# RA64500_jc20_rotary2.net
KiCad netlist of a schematic drawn in Altium Designer
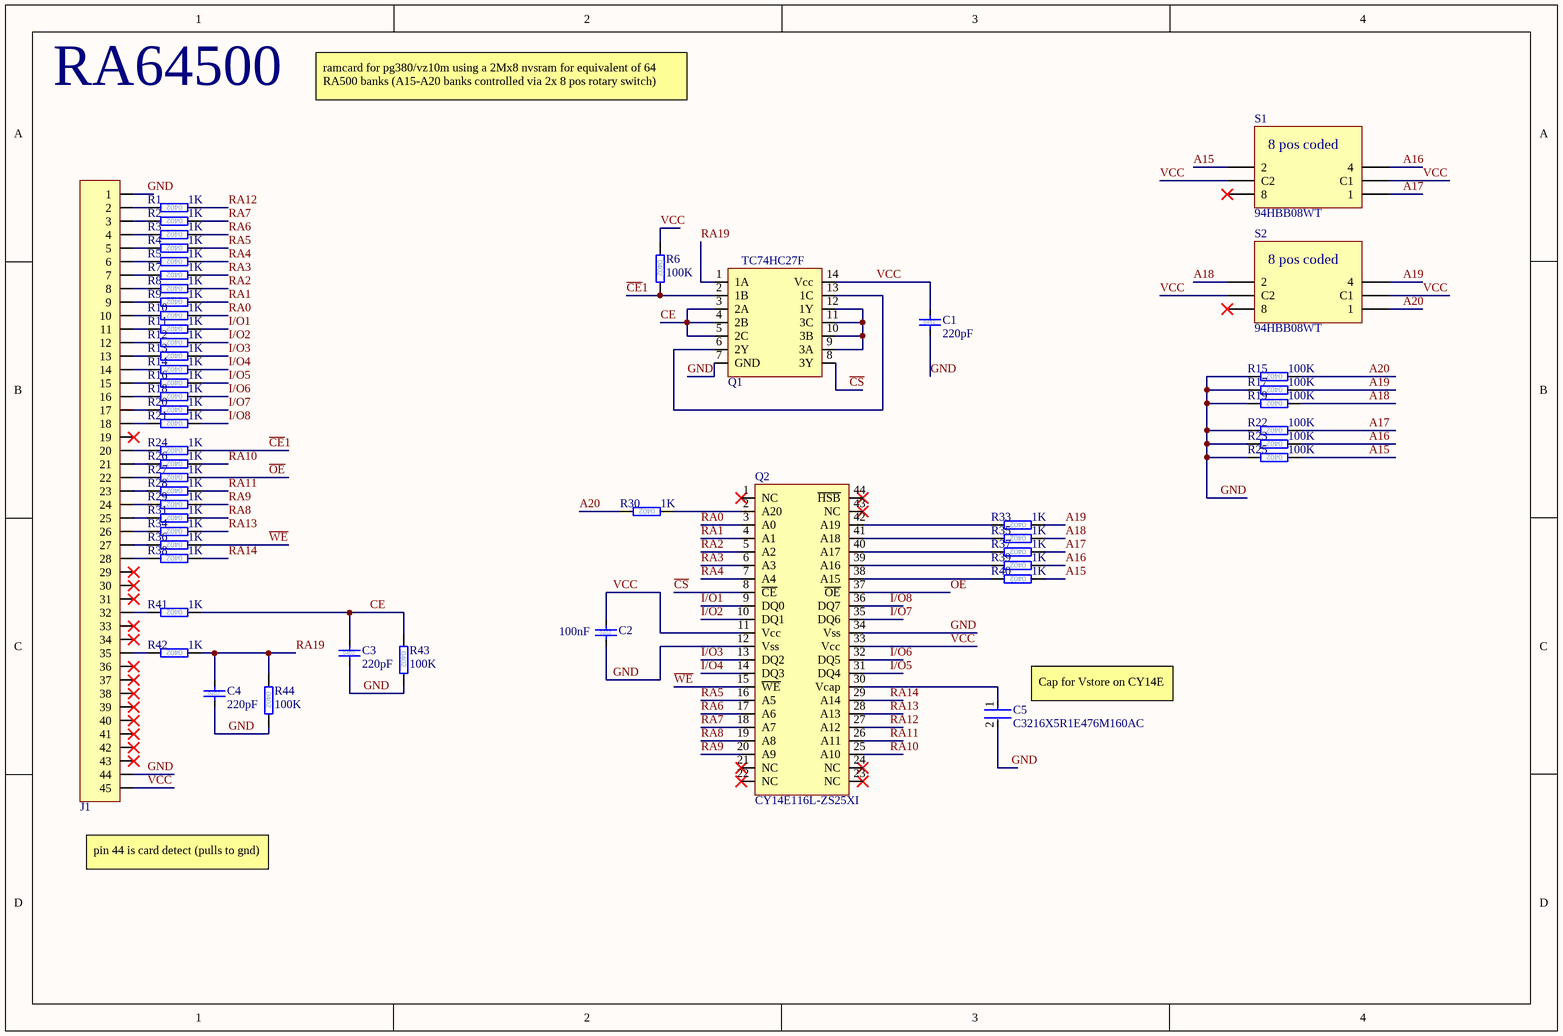
[diagram p0: RA64500_jc20_rotary2.SchDoc]

(export (version "E")
  (design (tool "Eeschema 10.0.6"))
  (components
    (comp (ref "C1")
      (value "220pF")
      (footprint "0402")
      (description "0402 220pF")
      (libsource (lib "ra500") (part "0402 Cap"))
    )
    (comp (ref "C2")
      (value "100nF")
      (footprint "0402")
      (description "0402 100nF")
      (libsource (lib "ra500") (part "0402 Cap"))
    )
    (comp (ref "C3")
      (value "220pF")
      (footprint "0402")
      (description "0402 220pF")
      (libsource (lib "ra500") (part "0402 Cap"))
    )
    (comp (ref "C4")
      (value "220pF")
      (footprint "0402")
      (description "0402 220pF")
      (libsource (lib "ra500") (part "0402 Cap"))
    )
    (comp (ref "C5")
      (value "C3216X5R1E476M160AC")
      (footprint "FP-C3216-160-0_2-MFG")
      (description "Multilayer Ceramic Capacitors 47uF ±20% 25V X5R SMD 1206")
      (fields (field (name "VOLTAGE") "25V") (field (name "TOLERANCE") "20%"))
      (libsource (lib "Altium Content Vault") (part "11868f565c42a9108669ba33697ecf6"))
    )
    (comp (ref "J1")
      (value "JC20-C45S-F1-A1")
      (footprint "JC20-C45S-F1-A1")
      (description "45 Pin 1mm pitch connector")
      (libsource (lib "ra500") (part "JC20-C45S-F1-A1"))
    )
    (comp (ref "Q1")
      (value "TC74HC27F")
      (footprint "SOP127P780X190-14N")
      (description "Triple 3-input NOR Gate")
      (libsource (lib "ra500") (part "TC74HC27F"))
    )
    (comp (ref "Q2")
      (value "CY14E116L-ZS25XI")
      (footprint "SOP80P1183X119-44N")
      (description "2Mx8 Bit nvSRAM")
      (libsource (lib "ra500") (part "CY14E116L-ZS25XI"))
    )
    (comp (ref "R1")
      (value "1K")
      (footprint "0402")
      (description "0402 1K")
      (libsource (lib "ra500") (part "0402 Res"))
    )
    (comp (ref "R2")
      (value "1K")
      (footprint "0402")
      (description "0402 1K")
      (libsource (lib "ra500") (part "0402 Res"))
    )
    (comp (ref "R3")
      (value "1K")
      (footprint "0402")
      (description "0402 1K")
      (libsource (lib "ra500") (part "0402 Res"))
    )
    (comp (ref "R4")
      (value "1K")
      (footprint "0402")
      (description "0402 1K")
      (libsource (lib "ra500") (part "0402 Res"))
    )
    (comp (ref "R5")
      (value "1K")
      (footprint "0402")
      (description "0402 1K")
      (libsource (lib "ra500") (part "0402 Res"))
    )
    (comp (ref "R6")
      (value "100K")
      (footprint "0402")
      (description "0402 100K")
      (libsource (lib "ra500") (part "0402 Res"))
    )
    (comp (ref "R7")
      (value "1K")
      (footprint "0402")
      (description "0402 1K")
      (libsource (lib "ra500") (part "0402 Res"))
    )
    (comp (ref "R8")
      (value "1K")
      (footprint "0402")
      (description "0402 1K")
      (libsource (lib "ra500") (part "0402 Res"))
    )
    (comp (ref "R9")
      (value "1K")
      (footprint "0402")
      (description "0402 1K")
      (libsource (lib "ra500") (part "0402 Res"))
    )
    (comp (ref "R10")
      (value "1K")
      (footprint "0402")
      (description "0402 1K")
      (libsource (lib "ra500") (part "0402 Res"))
    )
    (comp (ref "R11")
      (value "1K")
      (footprint "0402")
      (description "0402 1K")
      (libsource (lib "ra500") (part "0402 Res"))
    )
    (comp (ref "R12")
      (value "1K")
      (footprint "0402")
      (description "0402 1K")
      (libsource (lib "ra500") (part "0402 Res"))
    )
    (comp (ref "R13")
      (value "1K")
      (footprint "0402")
      (description "0402 1K")
      (libsource (lib "ra500") (part "0402 Res"))
    )
    (comp (ref "R14")
      (value "1K")
      (footprint "0402")
      (description "0402 1K")
      (libsource (lib "ra500") (part "0402 Res"))
    )
    (comp (ref "R15")
      (value "100K")
      (footprint "0402")
      (description "0402 100K")
      (libsource (lib "ra500") (part "0402 Res"))
    )
    (comp (ref "R16")
      (value "1K")
      (footprint "0402")
      (description "0402 1K")
      (libsource (lib "ra500") (part "0402 Res"))
    )
    (comp (ref "R17")
      (value "100K")
      (footprint "0402")
      (description "0402 100K")
      (libsource (lib "ra500") (part "0402 Res"))
    )
    (comp (ref "R18")
      (value "1K")
      (footprint "0402")
      (description "0402 1K")
      (libsource (lib "ra500") (part "0402 Res"))
    )
    (comp (ref "R19")
      (value "100K")
      (footprint "0402")
      (description "0402 100K")
      (libsource (lib "ra500") (part "0402 Res"))
    )
    (comp (ref "R20")
      (value "1K")
      (footprint "0402")
      (description "0402 1K")
      (libsource (lib "ra500") (part "0402 Res"))
    )
    (comp (ref "R21")
      (value "1K")
      (footprint "0402")
      (description "0402 1K")
      (libsource (lib "ra500") (part "0402 Res"))
    )
    (comp (ref "R22")
      (value "100K")
      (footprint "0402")
      (description "0402 100K")
      (libsource (lib "ra500") (part "0402 Res"))
    )
    (comp (ref "R23")
      (value "100K")
      (footprint "0402")
      (description "0402 100K")
      (libsource (lib "ra500") (part "0402 Res"))
    )
    (comp (ref "R24")
      (value "1K")
      (footprint "0402")
      (description "0402 1K")
      (libsource (lib "ra500") (part "0402 Res"))
    )
    (comp (ref "R25")
      (value "100K")
      (footprint "0402")
      (description "0402 100K")
      (libsource (lib "ra500") (part "0402 Res"))
    )
    (comp (ref "R26")
      (value "1K")
      (footprint "0402")
      (description "0402 1K")
      (libsource (lib "ra500") (part "0402 Res"))
    )
    (comp (ref "R27")
      (value "1K")
      (footprint "0402")
      (description "0402 1K")
      (libsource (lib "ra500") (part "0402 Res"))
    )
    (comp (ref "R28")
      (value "1K")
      (footprint "0402")
      (description "0402 1K")
      (libsource (lib "ra500") (part "0402 Res"))
    )
    (comp (ref "R29")
      (value "1K")
      (footprint "0402")
      (description "0402 1K")
      (libsource (lib "ra500") (part "0402 Res"))
    )
    (comp (ref "R30")
      (value "1K")
      (footprint "0402")
      (description "0402 1K")
      (libsource (lib "ra500") (part "0402 Res"))
    )
    (comp (ref "R31")
      (value "1K")
      (footprint "0402")
      (description "0402 1K")
      (libsource (lib "ra500") (part "0402 Res"))
    )
    (comp (ref "R33")
      (value "1K")
      (footprint "0402")
      (description "0402 1K")
      (libsource (lib "ra500") (part "0402 Res"))
    )
    (comp (ref "R34")
      (value "1K")
      (footprint "0402")
      (description "0402 1K")
      (libsource (lib "ra500") (part "0402 Res"))
    )
    (comp (ref "R35")
      (value "1K")
      (footprint "0402")
      (description "0402 1K")
      (libsource (lib "ra500") (part "0402 Res"))
    )
    (comp (ref "R36")
      (value "1K")
      (footprint "0402")
      (description "0402 1K")
      (libsource (lib "ra500") (part "0402 Res"))
    )
    (comp (ref "R37")
      (value "1K")
      (footprint "0402")
      (description "0402 1K")
      (libsource (lib "ra500") (part "0402 Res"))
    )
    (comp (ref "R38")
      (value "1K")
      (footprint "0402")
      (description "0402 1K")
      (libsource (lib "ra500") (part "0402 Res"))
    )
    (comp (ref "R39")
      (value "1K")
      (footprint "0402")
      (description "0402 1K")
      (libsource (lib "ra500") (part "0402 Res"))
    )
    (comp (ref "R40")
      (value "1K")
      (footprint "0402")
      (description "0402 1K")
      (libsource (lib "ra500") (part "0402 Res"))
    )
    (comp (ref "R41")
      (value "1K")
      (footprint "0402")
      (description "0402 1K")
      (libsource (lib "ra500") (part "0402 Res"))
    )
    (comp (ref "R42")
      (value "1K")
      (footprint "0402")
      (description "0402 1K")
      (libsource (lib "ra500") (part "0402 Res"))
    )
    (comp (ref "R43")
      (value "100K")
      (footprint "0402")
      (description "0402 100K")
      (libsource (lib "ra500") (part "0402 Res"))
    )
    (comp (ref "R44")
      (value "100K")
      (footprint "0402")
      (description "0402 100K")
      (libsource (lib "ra500") (part "0402 Res"))
    )
    (comp (ref "S1")
      (value "94HBB08WT")
      (footprint "94HBB08WT")
      (description "8 pos rotary coded switch")
      (libsource (lib "ra500") (part "94HBB08WT"))
    )
    (comp (ref "S2")
      (value "94HBB08WT")
      (footprint "94HBB08WT")
      (description "8 pos rotary coded switch")
      (libsource (lib "ra500") (part "94HBB08WT"))
    )
  )
  (nets
    (net (code "1") (name "/A15") (class "Default")
      (node (ref "R25") (pin "1") (pinfunction "R_1") (pintype "passive"))
      (node (ref "R40") (pin "1") (pinfunction "R_1") (pintype "passive"))
      (node (ref "S1") (pin "4") (pinfunction "2_4") (pintype "passive"))
    )
    (net (code "2") (name "/A16") (class "Default")
      (node (ref "R23") (pin "1") (pinfunction "R_1") (pintype "passive"))
      (node (ref "R39") (pin "1") (pinfunction "R_1") (pintype "passive"))
      (node (ref "S1") (pin "3") (pinfunction "4_3") (pintype "passive"))
    )
    (net (code "3") (name "/A17") (class "Default")
      (node (ref "R22") (pin "1") (pinfunction "R_1") (pintype "passive"))
      (node (ref "R37") (pin "1") (pinfunction "R_1") (pintype "passive"))
      (node (ref "S1") (pin "1") (pinfunction "1_1") (pintype "passive"))
    )
    (net (code "4") (name "/A18") (class "Default")
      (node (ref "R19") (pin "1") (pinfunction "R_1") (pintype "passive"))
      (node (ref "R35") (pin "1") (pinfunction "R_1") (pintype "passive"))
      (node (ref "S2") (pin "4") (pinfunction "2_4") (pintype "passive"))
    )
    (net (code "5") (name "/A19") (class "Default")
      (node (ref "R17") (pin "1") (pinfunction "R_1") (pintype "passive"))
      (node (ref "R33") (pin "1") (pinfunction "R_1") (pintype "passive"))
      (node (ref "S2") (pin "3") (pinfunction "4_3") (pintype "passive"))
    )
    (net (code "6") (name "/A20") (class "Default")
      (node (ref "R15") (pin "1") (pinfunction "R_1") (pintype "passive"))
      (node (ref "R30") (pin "2") (pinfunction "R_2") (pintype "passive"))
      (node (ref "S2") (pin "1") (pinfunction "1_1") (pintype "passive"))
    )
    (net (code "7") (name "/CE") (class "Default")
      (node (ref "C3") (pin "2") (pinfunction "2_2") (pintype "passive"))
      (node (ref "Q1") (pin "3") (pinfunction "2A_3") (pintype "passive"))
      (node (ref "Q1") (pin "4") (pinfunction "2B_4") (pintype "passive"))
      (node (ref "Q1") (pin "5") (pinfunction "2C_5") (pintype "passive"))
      (node (ref "R41") (pin "1") (pinfunction "R_1") (pintype "passive"))
      (node (ref "R43") (pin "1") (pinfunction "R_1") (pintype "passive"))
    )
    (net (code "8") (name "/GND") (class "Default")
      (node (ref "C1") (pin "1") (pinfunction "1_1") (pintype "passive"))
      (node (ref "C2") (pin "1") (pinfunction "1_1") (pintype "passive"))
      (node (ref "C3") (pin "1") (pinfunction "1_1") (pintype "passive"))
      (node (ref "C4") (pin "1") (pinfunction "1_1") (pintype "passive"))
      (node (ref "C5") (pin "2") (pinfunction "2_2") (pintype "passive"))
      (node (ref "J1") (pin "1") (pinfunction "1_1") (pintype "passive"))
      (node (ref "J1") (pin "44") (pinfunction "44_44") (pintype "passive"))
      (node (ref "Q1") (pin "7") (pinfunction "GND_7") (pintype "passive"))
      (node (ref "Q2") (pin "12") (pinfunction "Vss_12") (pintype "passive"))
      (node (ref "Q2") (pin "34") (pinfunction "Vss_34") (pintype "passive"))
      (node (ref "R15") (pin "2") (pinfunction "R_2") (pintype "passive"))
      (node (ref "R17") (pin "2") (pinfunction "R_2") (pintype "passive"))
      (node (ref "R19") (pin "2") (pinfunction "R_2") (pintype "passive"))
      (node (ref "R22") (pin "2") (pinfunction "R_2") (pintype "passive"))
      (node (ref "R23") (pin "2") (pinfunction "R_2") (pintype "passive"))
      (node (ref "R25") (pin "2") (pinfunction "R_2") (pintype "passive"))
      (node (ref "R43") (pin "2") (pinfunction "R_2") (pintype "passive"))
      (node (ref "R44") (pin "2") (pinfunction "R_2") (pintype "passive"))
    )
    (net (code "9") (name "/I{slash}O1") (class "Default")
      (node (ref "Q2") (pin "9") (pinfunction "DQ0_9") (pintype "passive"))
      (node (ref "R11") (pin "1") (pinfunction "R_1") (pintype "passive"))
    )
    (net (code "10") (name "/I{slash}O2") (class "Default")
      (node (ref "Q2") (pin "10") (pinfunction "DQ1_10") (pintype "passive"))
      (node (ref "R12") (pin "1") (pinfunction "R_1") (pintype "passive"))
    )
    (net (code "11") (name "/I{slash}O3") (class "Default")
      (node (ref "Q2") (pin "13") (pinfunction "DQ2_13") (pintype "passive"))
      (node (ref "R13") (pin "1") (pinfunction "R_1") (pintype "passive"))
    )
    (net (code "12") (name "/I{slash}O4") (class "Default")
      (node (ref "Q2") (pin "14") (pinfunction "DQ3_14") (pintype "passive"))
      (node (ref "R14") (pin "1") (pinfunction "R_1") (pintype "passive"))
    )
    (net (code "13") (name "/I{slash}O5") (class "Default")
      (node (ref "Q2") (pin "31") (pinfunction "DQ4_31") (pintype "passive"))
      (node (ref "R16") (pin "1") (pinfunction "R_1") (pintype "passive"))
    )
    (net (code "14") (name "/I{slash}O6") (class "Default")
      (node (ref "Q2") (pin "32") (pinfunction "DQ5_32") (pintype "passive"))
      (node (ref "R18") (pin "1") (pinfunction "R_1") (pintype "passive"))
    )
    (net (code "15") (name "/I{slash}O7") (class "Default")
      (node (ref "Q2") (pin "35") (pinfunction "DQ6_35") (pintype "passive"))
      (node (ref "R20") (pin "1") (pinfunction "R_1") (pintype "passive"))
    )
    (net (code "16") (name "/I{slash}O8") (class "Default")
      (node (ref "Q2") (pin "36") (pinfunction "DQ7_36") (pintype "passive"))
      (node (ref "R21") (pin "1") (pinfunction "R_1") (pintype "passive"))
    )
    (net (code "17") (name "/RA0") (class "Default")
      (node (ref "Q2") (pin "3") (pinfunction "A0_3") (pintype "passive"))
      (node (ref "R10") (pin "1") (pinfunction "R_1") (pintype "passive"))
    )
    (net (code "18") (name "/RA1") (class "Default")
      (node (ref "Q2") (pin "4") (pinfunction "A1_4") (pintype "passive"))
      (node (ref "R9") (pin "1") (pinfunction "R_1") (pintype "passive"))
    )
    (net (code "19") (name "/RA2") (class "Default")
      (node (ref "Q2") (pin "5") (pinfunction "A2_5") (pintype "passive"))
      (node (ref "R8") (pin "1") (pinfunction "R_1") (pintype "passive"))
    )
    (net (code "20") (name "/RA3") (class "Default")
      (node (ref "Q2") (pin "6") (pinfunction "A3_6") (pintype "passive"))
      (node (ref "R7") (pin "1") (pinfunction "R_1") (pintype "passive"))
    )
    (net (code "21") (name "/RA4") (class "Default")
      (node (ref "Q2") (pin "7") (pinfunction "A4_7") (pintype "passive"))
      (node (ref "R5") (pin "1") (pinfunction "R_1") (pintype "passive"))
    )
    (net (code "22") (name "/RA5") (class "Default")
      (node (ref "Q2") (pin "16") (pinfunction "A5_16") (pintype "passive"))
      (node (ref "R4") (pin "1") (pinfunction "R_1") (pintype "passive"))
    )
    (net (code "23") (name "/RA6") (class "Default")
      (node (ref "Q2") (pin "17") (pinfunction "A6_17") (pintype "passive"))
      (node (ref "R3") (pin "1") (pinfunction "R_1") (pintype "passive"))
    )
    (net (code "24") (name "/RA7") (class "Default")
      (node (ref "Q2") (pin "18") (pinfunction "A7_18") (pintype "passive"))
      (node (ref "R2") (pin "1") (pinfunction "R_1") (pintype "passive"))
    )
    (net (code "25") (name "/RA8") (class "Default")
      (node (ref "Q2") (pin "19") (pinfunction "A8_19") (pintype "passive"))
      (node (ref "R31") (pin "1") (pinfunction "R_1") (pintype "passive"))
    )
    (net (code "26") (name "/RA9") (class "Default")
      (node (ref "Q2") (pin "20") (pinfunction "A9_20") (pintype "passive"))
      (node (ref "R29") (pin "1") (pinfunction "R_1") (pintype "passive"))
    )
    (net (code "27") (name "/RA10") (class "Default")
      (node (ref "Q2") (pin "25") (pinfunction "A10_25") (pintype "passive"))
      (node (ref "R26") (pin "1") (pinfunction "R_1") (pintype "passive"))
    )
    (net (code "28") (name "/RA11") (class "Default")
      (node (ref "Q2") (pin "26") (pinfunction "A11_26") (pintype "passive"))
      (node (ref "R28") (pin "1") (pinfunction "R_1") (pintype "passive"))
    )
    (net (code "29") (name "/RA12") (class "Default")
      (node (ref "Q2") (pin "27") (pinfunction "A12_27") (pintype "passive"))
      (node (ref "R1") (pin "1") (pinfunction "R_1") (pintype "passive"))
    )
    (net (code "30") (name "/RA13") (class "Default")
      (node (ref "Q2") (pin "28") (pinfunction "A13_28") (pintype "passive"))
      (node (ref "R34") (pin "1") (pinfunction "R_1") (pintype "passive"))
    )
    (net (code "31") (name "/RA14") (class "Default")
      (node (ref "Q2") (pin "29") (pinfunction "A14_29") (pintype "passive"))
      (node (ref "R38") (pin "1") (pinfunction "R_1") (pintype "passive"))
    )
    (net (code "32") (name "/RA19") (class "Default")
      (node (ref "C4") (pin "2") (pinfunction "2_2") (pintype "passive"))
      (node (ref "Q1") (pin "1") (pinfunction "1A_1") (pintype "passive"))
      (node (ref "R42") (pin "1") (pinfunction "R_1") (pintype "passive"))
      (node (ref "R44") (pin "1") (pinfunction "R_1") (pintype "passive"))
    )
    (net (code "33") (name "/VCC") (class "Default")
      (node (ref "C1") (pin "2") (pinfunction "2_2") (pintype "passive"))
      (node (ref "C2") (pin "2") (pinfunction "2_2") (pintype "passive"))
      (node (ref "J1") (pin "45") (pinfunction "45_45") (pintype "passive"))
      (node (ref "Q1") (pin "14") (pinfunction "Vcc_14") (pintype "passive"))
      (node (ref "Q2") (pin "11") (pinfunction "Vcc_11") (pintype "passive"))
      (node (ref "Q2") (pin "33") (pinfunction "Vcc_33") (pintype "passive"))
      (node (ref "R6") (pin "1") (pinfunction "R_1") (pintype "passive"))
      (node (ref "S1") (pin "2") (pinfunction "C1_2") (pintype "passive"))
      (node (ref "S1") (pin "5") (pinfunction "C2_5") (pintype "passive"))
      (node (ref "S2") (pin "2") (pinfunction "C1_2") (pintype "passive"))
      (node (ref "S2") (pin "5") (pinfunction "C2_5") (pintype "passive"))
    )
    (net (code "34") (name "/~{CE}1") (class "Default")
      (node (ref "Q1") (pin "2") (pinfunction "1B_2") (pintype "passive"))
      (node (ref "R24") (pin "1") (pinfunction "R_1") (pintype "passive"))
      (node (ref "R6") (pin "2") (pinfunction "R_2") (pintype "passive"))
    )
    (net (code "35") (name "/~{CS}") (class "Default")
      (node (ref "Q1") (pin "8") (pinfunction "3Y_8") (pintype "passive"))
      (node (ref "Q2") (pin "8") (pinfunction "~{CE}_8") (pintype "passive"))
    )
    (net (code "36") (name "/~{OE}") (class "Default")
      (node (ref "Q2") (pin "37") (pinfunction "~{OE}_37") (pintype "passive"))
      (node (ref "R27") (pin "1") (pinfunction "R_1") (pintype "passive"))
    )
    (net (code "37") (name "/~{WE}") (class "Default")
      (node (ref "Q2") (pin "15") (pinfunction "~{WE}_15") (pintype "passive"))
      (node (ref "R36") (pin "1") (pinfunction "R_1") (pintype "passive"))
    )
    (net (code "38") (name "Net-(J1-Pad2)") (class "Default")
      (node (ref "J1") (pin "2") (pinfunction "2_2") (pintype "passive"))
      (node (ref "R1") (pin "2") (pinfunction "R_2") (pintype "passive"))
    )
    (net (code "39") (name "Net-(J1-Pad3)") (class "Default")
      (node (ref "J1") (pin "3") (pinfunction "3_3") (pintype "passive"))
      (node (ref "R2") (pin "2") (pinfunction "R_2") (pintype "passive"))
    )
    (net (code "40") (name "Net-(J1-Pad4)") (class "Default")
      (node (ref "J1") (pin "4") (pinfunction "4_4") (pintype "passive"))
      (node (ref "R3") (pin "2") (pinfunction "R_2") (pintype "passive"))
    )
    (net (code "41") (name "Net-(J1-Pad5)") (class "Default")
      (node (ref "J1") (pin "5") (pinfunction "5_5") (pintype "passive"))
      (node (ref "R4") (pin "2") (pinfunction "R_2") (pintype "passive"))
    )
    (net (code "42") (name "Net-(J1-Pad6)") (class "Default")
      (node (ref "J1") (pin "6") (pinfunction "6_6") (pintype "passive"))
      (node (ref "R5") (pin "2") (pinfunction "R_2") (pintype "passive"))
    )
    (net (code "43") (name "Net-(J1-Pad7)") (class "Default")
      (node (ref "J1") (pin "7") (pinfunction "7_7") (pintype "passive"))
      (node (ref "R7") (pin "2") (pinfunction "R_2") (pintype "passive"))
    )
    (net (code "44") (name "Net-(J1-Pad8)") (class "Default")
      (node (ref "J1") (pin "8") (pinfunction "8_8") (pintype "passive"))
      (node (ref "R8") (pin "2") (pinfunction "R_2") (pintype "passive"))
    )
    (net (code "45") (name "Net-(J1-Pad9)") (class "Default")
      (node (ref "J1") (pin "9") (pinfunction "9_9") (pintype "passive"))
      (node (ref "R9") (pin "2") (pinfunction "R_2") (pintype "passive"))
    )
    (net (code "46") (name "Net-(J1-Pad10)") (class "Default")
      (node (ref "J1") (pin "10") (pinfunction "10_10") (pintype "passive"))
      (node (ref "R10") (pin "2") (pinfunction "R_2") (pintype "passive"))
    )
    (net (code "47") (name "Net-(J1-Pad11)") (class "Default")
      (node (ref "J1") (pin "11") (pinfunction "11_11") (pintype "passive"))
      (node (ref "R11") (pin "2") (pinfunction "R_2") (pintype "passive"))
    )
    (net (code "48") (name "Net-(J1-Pad12)") (class "Default")
      (node (ref "J1") (pin "12") (pinfunction "12_12") (pintype "passive"))
      (node (ref "R12") (pin "2") (pinfunction "R_2") (pintype "passive"))
    )
    (net (code "49") (name "Net-(J1-Pad13)") (class "Default")
      (node (ref "J1") (pin "13") (pinfunction "13_13") (pintype "passive"))
      (node (ref "R13") (pin "2") (pinfunction "R_2") (pintype "passive"))
    )
    (net (code "50") (name "Net-(J1-Pad14)") (class "Default")
      (node (ref "J1") (pin "14") (pinfunction "14_14") (pintype "passive"))
      (node (ref "R14") (pin "2") (pinfunction "R_2") (pintype "passive"))
    )
    (net (code "51") (name "Net-(J1-Pad15)") (class "Default")
      (node (ref "J1") (pin "15") (pinfunction "15_15") (pintype "passive"))
      (node (ref "R16") (pin "2") (pinfunction "R_2") (pintype "passive"))
    )
    (net (code "52") (name "Net-(J1-Pad16)") (class "Default")
      (node (ref "J1") (pin "16") (pinfunction "16_16") (pintype "passive"))
      (node (ref "R18") (pin "2") (pinfunction "R_2") (pintype "passive"))
    )
    (net (code "53") (name "Net-(J1-Pad17)") (class "Default")
      (node (ref "J1") (pin "17") (pinfunction "17_17") (pintype "passive"))
      (node (ref "R20") (pin "2") (pinfunction "R_2") (pintype "passive"))
    )
    (net (code "54") (name "Net-(J1-Pad18)") (class "Default")
      (node (ref "J1") (pin "18") (pinfunction "18_18") (pintype "passive"))
      (node (ref "R21") (pin "2") (pinfunction "R_2") (pintype "passive"))
    )
    (net (code "55") (name "Net-(J1-Pad20)") (class "Default")
      (node (ref "J1") (pin "20") (pinfunction "20_20") (pintype "passive"))
      (node (ref "R24") (pin "2") (pinfunction "R_2") (pintype "passive"))
    )
    (net (code "56") (name "Net-(J1-Pad21)") (class "Default")
      (node (ref "J1") (pin "21") (pinfunction "21_21") (pintype "passive"))
      (node (ref "R26") (pin "2") (pinfunction "R_2") (pintype "passive"))
    )
    (net (code "57") (name "Net-(J1-Pad22)") (class "Default")
      (node (ref "J1") (pin "22") (pinfunction "22_22") (pintype "passive"))
      (node (ref "R27") (pin "2") (pinfunction "R_2") (pintype "passive"))
    )
    (net (code "58") (name "Net-(J1-Pad23)") (class "Default")
      (node (ref "J1") (pin "23") (pinfunction "23_23") (pintype "passive"))
      (node (ref "R28") (pin "2") (pinfunction "R_2") (pintype "passive"))
    )
    (net (code "59") (name "Net-(J1-Pad24)") (class "Default")
      (node (ref "J1") (pin "24") (pinfunction "24_24") (pintype "passive"))
      (node (ref "R29") (pin "2") (pinfunction "R_2") (pintype "passive"))
    )
    (net (code "60") (name "Net-(J1-Pad25)") (class "Default")
      (node (ref "J1") (pin "25") (pinfunction "25_25") (pintype "passive"))
      (node (ref "R31") (pin "2") (pinfunction "R_2") (pintype "passive"))
    )
    (net (code "61") (name "Net-(J1-Pad26)") (class "Default")
      (node (ref "J1") (pin "26") (pinfunction "26_26") (pintype "passive"))
      (node (ref "R34") (pin "2") (pinfunction "R_2") (pintype "passive"))
    )
    (net (code "62") (name "Net-(J1-Pad27)") (class "Default")
      (node (ref "J1") (pin "27") (pinfunction "27_27") (pintype "passive"))
      (node (ref "R36") (pin "2") (pinfunction "R_2") (pintype "passive"))
    )
    (net (code "63") (name "Net-(J1-Pad28)") (class "Default")
      (node (ref "J1") (pin "28") (pinfunction "28_28") (pintype "passive"))
      (node (ref "R38") (pin "2") (pinfunction "R_2") (pintype "passive"))
    )
    (net (code "64") (name "Net-(J1-Pad32)") (class "Default")
      (node (ref "J1") (pin "32") (pinfunction "32_32") (pintype "passive"))
      (node (ref "R41") (pin "2") (pinfunction "R_2") (pintype "passive"))
    )
    (net (code "65") (name "Net-(J1-Pad35)") (class "Default")
      (node (ref "J1") (pin "35") (pinfunction "35_35") (pintype "passive"))
      (node (ref "R42") (pin "2") (pinfunction "R_2") (pintype "passive"))
    )
    (net (code "66") (name "Net-(Q1-1C)") (class "Default")
      (node (ref "Q1") (pin "13") (pinfunction "1C_13") (pintype "passive"))
      (node (ref "Q1") (pin "6") (pinfunction "2Y_6") (pintype "passive"))
    )
    (net (code "67") (name "Net-(Q1-1Y)") (class "Default")
      (node (ref "Q1") (pin "10") (pinfunction "3B_10") (pintype "passive"))
      (node (ref "Q1") (pin "11") (pinfunction "3C_11") (pintype "passive"))
      (node (ref "Q1") (pin "12") (pinfunction "1Y_12") (pintype "passive"))
      (node (ref "Q1") (pin "9") (pinfunction "3A_9") (pintype "passive"))
    )
    (net (code "68") (name "Net-(Q2-A15)") (class "Default")
      (node (ref "Q2") (pin "38") (pinfunction "A15_38") (pintype "passive"))
      (node (ref "R40") (pin "2") (pinfunction "R_2") (pintype "passive"))
    )
    (net (code "69") (name "Net-(Q2-A16)") (class "Default")
      (node (ref "Q2") (pin "39") (pinfunction "A16_39") (pintype "passive"))
      (node (ref "R39") (pin "2") (pinfunction "R_2") (pintype "passive"))
    )
    (net (code "70") (name "Net-(Q2-A17)") (class "Default")
      (node (ref "Q2") (pin "40") (pinfunction "A17_40") (pintype "passive"))
      (node (ref "R37") (pin "2") (pinfunction "R_2") (pintype "passive"))
    )
    (net (code "71") (name "Net-(Q2-A18)") (class "Default")
      (node (ref "Q2") (pin "41") (pinfunction "A18_41") (pintype "passive"))
      (node (ref "R35") (pin "2") (pinfunction "R_2") (pintype "passive"))
    )
    (net (code "72") (name "Net-(Q2-A19)") (class "Default")
      (node (ref "Q2") (pin "42") (pinfunction "A19_42") (pintype "passive"))
      (node (ref "R33") (pin "2") (pinfunction "R_2") (pintype "passive"))
    )
    (net (code "73") (name "Net-(Q2-A20)") (class "Default")
      (node (ref "Q2") (pin "2") (pinfunction "A20_2") (pintype "passive"))
      (node (ref "R30") (pin "1") (pinfunction "R_1") (pintype "passive"))
    )
    (net (code "74") (name "Net-(Q2-Vcap)") (class "Default")
      (node (ref "C5") (pin "1") (pinfunction "1_1") (pintype "passive"))
      (node (ref "Q2") (pin "30") (pinfunction "Vcap_30") (pintype "passive"))
    )
    (net (code "75") (name "unconnected-(J1-Pad19)") (class "Default")
      (node (ref "J1") (pin "19") (pinfunction "19_19") (pintype "passive+no_connect"))
    )
    (net (code "76") (name "unconnected-(J1-Pad29)") (class "Default")
      (node (ref "J1") (pin "29") (pinfunction "29_29") (pintype "passive+no_connect"))
    )
    (net (code "77") (name "unconnected-(J1-Pad30)") (class "Default")
      (node (ref "J1") (pin "30") (pinfunction "30_30") (pintype "passive+no_connect"))
    )
    (net (code "78") (name "unconnected-(J1-Pad31)") (class "Default")
      (node (ref "J1") (pin "31") (pinfunction "31_31") (pintype "passive+no_connect"))
    )
    (net (code "79") (name "unconnected-(J1-Pad33)") (class "Default")
      (node (ref "J1") (pin "33") (pinfunction "33_33") (pintype "passive+no_connect"))
    )
    (net (code "80") (name "unconnected-(J1-Pad34)") (class "Default")
      (node (ref "J1") (pin "34") (pinfunction "34_34") (pintype "passive+no_connect"))
    )
    (net (code "81") (name "unconnected-(J1-Pad36)") (class "Default")
      (node (ref "J1") (pin "36") (pinfunction "36_36") (pintype "passive+no_connect"))
    )
    (net (code "82") (name "unconnected-(J1-Pad37)") (class "Default")
      (node (ref "J1") (pin "37") (pinfunction "37_37") (pintype "passive+no_connect"))
    )
    (net (code "83") (name "unconnected-(J1-Pad38)") (class "Default")
      (node (ref "J1") (pin "38") (pinfunction "38_38") (pintype "passive+no_connect"))
    )
    (net (code "84") (name "unconnected-(J1-Pad39)") (class "Default")
      (node (ref "J1") (pin "39") (pinfunction "39_39") (pintype "passive+no_connect"))
    )
    (net (code "85") (name "unconnected-(J1-Pad40)") (class "Default")
      (node (ref "J1") (pin "40") (pinfunction "40_40") (pintype "passive+no_connect"))
    )
    (net (code "86") (name "unconnected-(J1-Pad41)") (class "Default")
      (node (ref "J1") (pin "41") (pinfunction "41_41") (pintype "passive+no_connect"))
    )
    (net (code "87") (name "unconnected-(J1-Pad42)") (class "Default")
      (node (ref "J1") (pin "42") (pinfunction "42_42") (pintype "passive+no_connect"))
    )
    (net (code "88") (name "unconnected-(J1-Pad43)") (class "Default")
      (node (ref "J1") (pin "43") (pinfunction "43_43") (pintype "passive+no_connect"))
    )
    (net (code "89") (name "unconnected-(Q2-NC-Pad1)") (class "Default")
      (node (ref "Q2") (pin "1") (pinfunction "NC_1") (pintype "passive+no_connect"))
    )
    (net (code "90") (name "unconnected-(Q2-NC-Pad21)") (class "Default")
      (node (ref "Q2") (pin "21") (pinfunction "NC_21") (pintype "passive+no_connect"))
    )
    (net (code "91") (name "unconnected-(Q2-NC-Pad22)") (class "Default")
      (node (ref "Q2") (pin "22") (pinfunction "NC_22") (pintype "passive+no_connect"))
    )
    (net (code "92") (name "unconnected-(Q2-NC-Pad23)") (class "Default")
      (node (ref "Q2") (pin "23") (pinfunction "NC_23") (pintype "passive+no_connect"))
    )
    (net (code "93") (name "unconnected-(Q2-NC-Pad24)") (class "Default")
      (node (ref "Q2") (pin "24") (pinfunction "NC_24") (pintype "passive+no_connect"))
    )
    (net (code "94") (name "unconnected-(Q2-NC-Pad43)") (class "Default")
      (node (ref "Q2") (pin "43") (pinfunction "NC_43") (pintype "passive+no_connect"))
    )
    (net (code "95") (name "unconnected-(Q2-~{HSB}-Pad44)") (class "Default")
      (node (ref "Q2") (pin "44") (pinfunction "~{HSB}_44") (pintype "passive+no_connect"))
    )
    (net (code "96") (name "unconnected-(S1-8-Pad6)") (class "Default")
      (node (ref "S1") (pin "6") (pinfunction "8_6") (pintype "passive+no_connect"))
    )
    (net (code "97") (name "unconnected-(S2-8-Pad6)") (class "Default")
      (node (ref "S2") (pin "6") (pinfunction "8_6") (pintype "passive+no_connect"))
    )
  )
)
